# Counter_Switch.net
KiCad netlist of a schematic drawn in Altium Designer
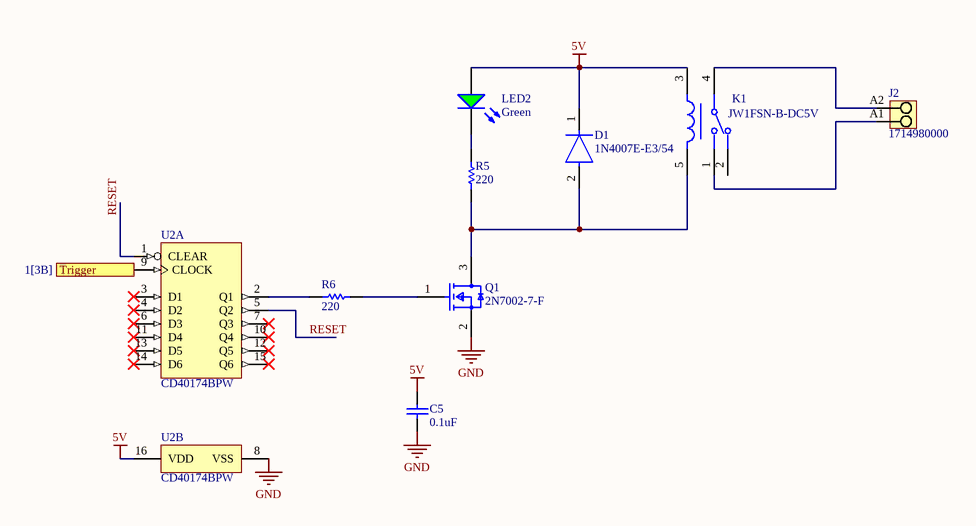
[diagram p0: Counter_Switch.SchDoc]

(export (version "E")
  (design (tool "Eeschema 10.0.6"))
  (components
    (comp (ref "C5")
      (value "0.1uF")
      (footprint "CAPC2013X145X50ML20T20")
      (fields (field (name "MANUFACTURER") "Vitramon") (field (name "PART NUMBER") "VJ0805Y104MXQCW1BC"))
      (libsource (lib "MDL") (part "CAP 0.1uF 10V 0805"))
    )
    (comp (ref "D1")
      (value "1N4007E-E3/54")
      (footprint "FP-1N4007E-E3-54-MFG")
      (description "DIODE GEN PURP 1KV 1A DO204AL")
      (libsource (lib "MDL") (part "Diode General Purpose 1N4007"))
    )
    (comp (ref "J2")
      (value "1714980000")
      (footprint "LM_3_5_135_02")
      (description "OMNIMATE Signal - series LM")
      (fields (field (name "MANUFACTURER") "Weidmueller"))
      (libsource (lib "MDL") (part "Terminal Block 2Pos"))
    )
    (comp (ref "K1")
      (value "JW1FSN-B-DC5V")
      (footprint "FP-JW1FSN-B-DC5V-MFG")
      (description "RELAY GEN PURPOSE SPDT 10A 5V")
      (libsource (lib "MDL") (part "RELAY SPDT 5V"))
    )
    (comp (ref "LED2")
      (value "Green")
      (footprint "KING-WP7113SGD_V")
      (description "LED Green, 62.5 mW, 25 mA, -40 to 85 degC, 2-Pin THD, RoHS, Bulk")
      (fields (field (name "MANUFACTURER") "Kingbright"))
      (libsource (lib "MDL") (part "LED 5mm Green"))
    )
    (comp (ref "Q1")
      (value "2N7002-7-F")
      (footprint "FP-SOT23-IPC_A")
      (description "MOSFET N-CH 60V 115MA SOT23-3")
      (fields (field (name "VOLTAGE") "60V"))
      (libsource (lib "MDL") (part "MOSFET 2N7002 SMD"))
    )
    (comp (ref "R5")
      (value "220")
      (footprint "RESC2013X60X30NL20T20")
      (fields (field (name "PART NUMBER") "SG73S2ATTD2200F") (field (name "MANUFACTURER") "KOA Speer"))
      (libsource (lib "MDL") (part "Res 220 Ohm 0.25W SMD"))
    )
    (comp (ref "R6")
      (value "220")
      (footprint "RESC2013X60X30NL20T20")
      (fields (field (name "PART NUMBER") "SG73S2ATTD2200F") (field (name "MANUFACTURER") "KOA Speer"))
      (libsource (lib "MDL") (part "Res 220 Ohm 0.25W SMD"))
    )
    (comp (ref "U2")
      (value "CD40174BPW")
      (footprint "PW0016A_M")
      (description "CMOS Hex D-Type Flip-Flop, PW0016A, TUBE")
      (fields
        (field (name "GENERIC PART NUMBER") "CD40174B")
        (field (name "MANUFACTURER") "Texas Instruments")
      )
      (libsource (lib "MDL") (part "IC CD4071"))
    )
  )
  (nets
    (net (code "1") (name "/RESET") (class "Default")
      (node (ref "U2") (pin "1") (pinfunction "CLEAR_1") (pintype "input"))
      (node (ref "U2") (pin "5") (pinfunction "Q2_5") (pintype "output"))
    )
    (net (code "2") (name "/Trigger") (class "Default")
      (node (ref "U2") (pin "9") (pinfunction "CLOCK_9") (pintype "input"))
    )
    (net (code "3") (name "5V") (class "Default")
      (node (ref "C5") (pin "2") (pinfunction "2_2") (pintype "passive"))
      (node (ref "D1") (pin "1") (pinfunction "C_1") (pintype "passive"))
      (node (ref "K1") (pin "3") (pinfunction "3_3") (pintype "passive"))
      (node (ref "LED2") (pin "1") (pinfunction "A_1") (pintype "passive"))
      (node (ref "U2") (pin "16") (pinfunction "VDD_16") (pintype "power_in"))
    )
    (net (code "4") (name "GND") (class "Default")
      (node (ref "C5") (pin "1") (pinfunction "1_1") (pintype "passive"))
      (node (ref "Q1") (pin "2") (pinfunction "S_2") (pintype "passive"))
      (node (ref "U2") (pin "8") (pinfunction "VSS_8") (pintype "power_in"))
    )
    (net (code "5") (name "Net-(D1-A)") (class "Default")
      (node (ref "D1") (pin "2") (pinfunction "A_2") (pintype "passive"))
      (node (ref "K1") (pin "5") (pinfunction "5_5") (pintype "passive"))
      (node (ref "Q1") (pin "3") (pinfunction "D_3") (pintype "passive"))
      (node (ref "R5") (pin "1") (pinfunction "1_1") (pintype "passive"))
    )
    (net (code "6") (name "Net-(J2-PadA1)") (class "Default")
      (node (ref "J2") (pin "A1") (pinfunction "A1_A1") (pintype "passive"))
      (node (ref "K1") (pin "1") (pinfunction "1_1") (pintype "passive"))
    )
    (net (code "7") (name "Net-(J2-PadA2)") (class "Default")
      (node (ref "J2") (pin "A2") (pinfunction "A2_A2") (pintype "passive"))
      (node (ref "K1") (pin "4") (pinfunction "4_4") (pintype "passive"))
    )
    (net (code "8") (name "Net-(LED2-K)") (class "Default")
      (node (ref "LED2") (pin "2") (pinfunction "K_2") (pintype "passive"))
      (node (ref "R5") (pin "2") (pinfunction "2_2") (pintype "passive"))
    )
    (net (code "9") (name "Net-(Q1-G)") (class "Default")
      (node (ref "Q1") (pin "1") (pinfunction "G_1") (pintype "passive"))
      (node (ref "R6") (pin "2") (pinfunction "2_2") (pintype "passive"))
    )
    (net (code "10") (name "Net-(U2A-Q1)") (class "Default")
      (node (ref "R6") (pin "1") (pinfunction "1_1") (pintype "passive"))
      (node (ref "U2") (pin "2") (pinfunction "Q1_2") (pintype "output"))
    )
    (net (code "11") (name "unconnected-(K1-Pad2)") (class "Default")
      (node (ref "K1") (pin "2") (pinfunction "2_2") (pintype "passive"))
    )
    (net (code "12") (name "unconnected-(U2A-D1-Pad3)") (class "Default")
      (node (ref "U2") (pin "3") (pinfunction "D1_3") (pintype "input+no_connect"))
    )
    (net (code "13") (name "unconnected-(U2A-D2-Pad4)") (class "Default")
      (node (ref "U2") (pin "4") (pinfunction "D2_4") (pintype "input+no_connect"))
    )
    (net (code "14") (name "unconnected-(U2A-D3-Pad6)") (class "Default")
      (node (ref "U2") (pin "6") (pinfunction "D3_6") (pintype "input+no_connect"))
    )
    (net (code "15") (name "unconnected-(U2A-D4-Pad11)") (class "Default")
      (node (ref "U2") (pin "11") (pinfunction "D4_11") (pintype "input+no_connect"))
    )
    (net (code "16") (name "unconnected-(U2A-D5-Pad13)") (class "Default")
      (node (ref "U2") (pin "13") (pinfunction "D5_13") (pintype "input+no_connect"))
    )
    (net (code "17") (name "unconnected-(U2A-D6-Pad14)") (class "Default")
      (node (ref "U2") (pin "14") (pinfunction "D6_14") (pintype "input+no_connect"))
    )
    (net (code "18") (name "unconnected-(U2A-Q3-Pad7)") (class "Default")
      (node (ref "U2") (pin "7") (pinfunction "Q3_7") (pintype "output+no_connect"))
    )
    (net (code "19") (name "unconnected-(U2A-Q4-Pad10)") (class "Default")
      (node (ref "U2") (pin "10") (pinfunction "Q4_10") (pintype "output+no_connect"))
    )
    (net (code "20") (name "unconnected-(U2A-Q5-Pad12)") (class "Default")
      (node (ref "U2") (pin "12") (pinfunction "Q5_12") (pintype "output+no_connect"))
    )
    (net (code "21") (name "unconnected-(U2A-Q6-Pad15)") (class "Default")
      (node (ref "U2") (pin "15") (pinfunction "Q6_15") (pintype "output+no_connect"))
    )
  )
)
